# Turntable.net
KiCad netlist of a schematic drawn in EAGLE
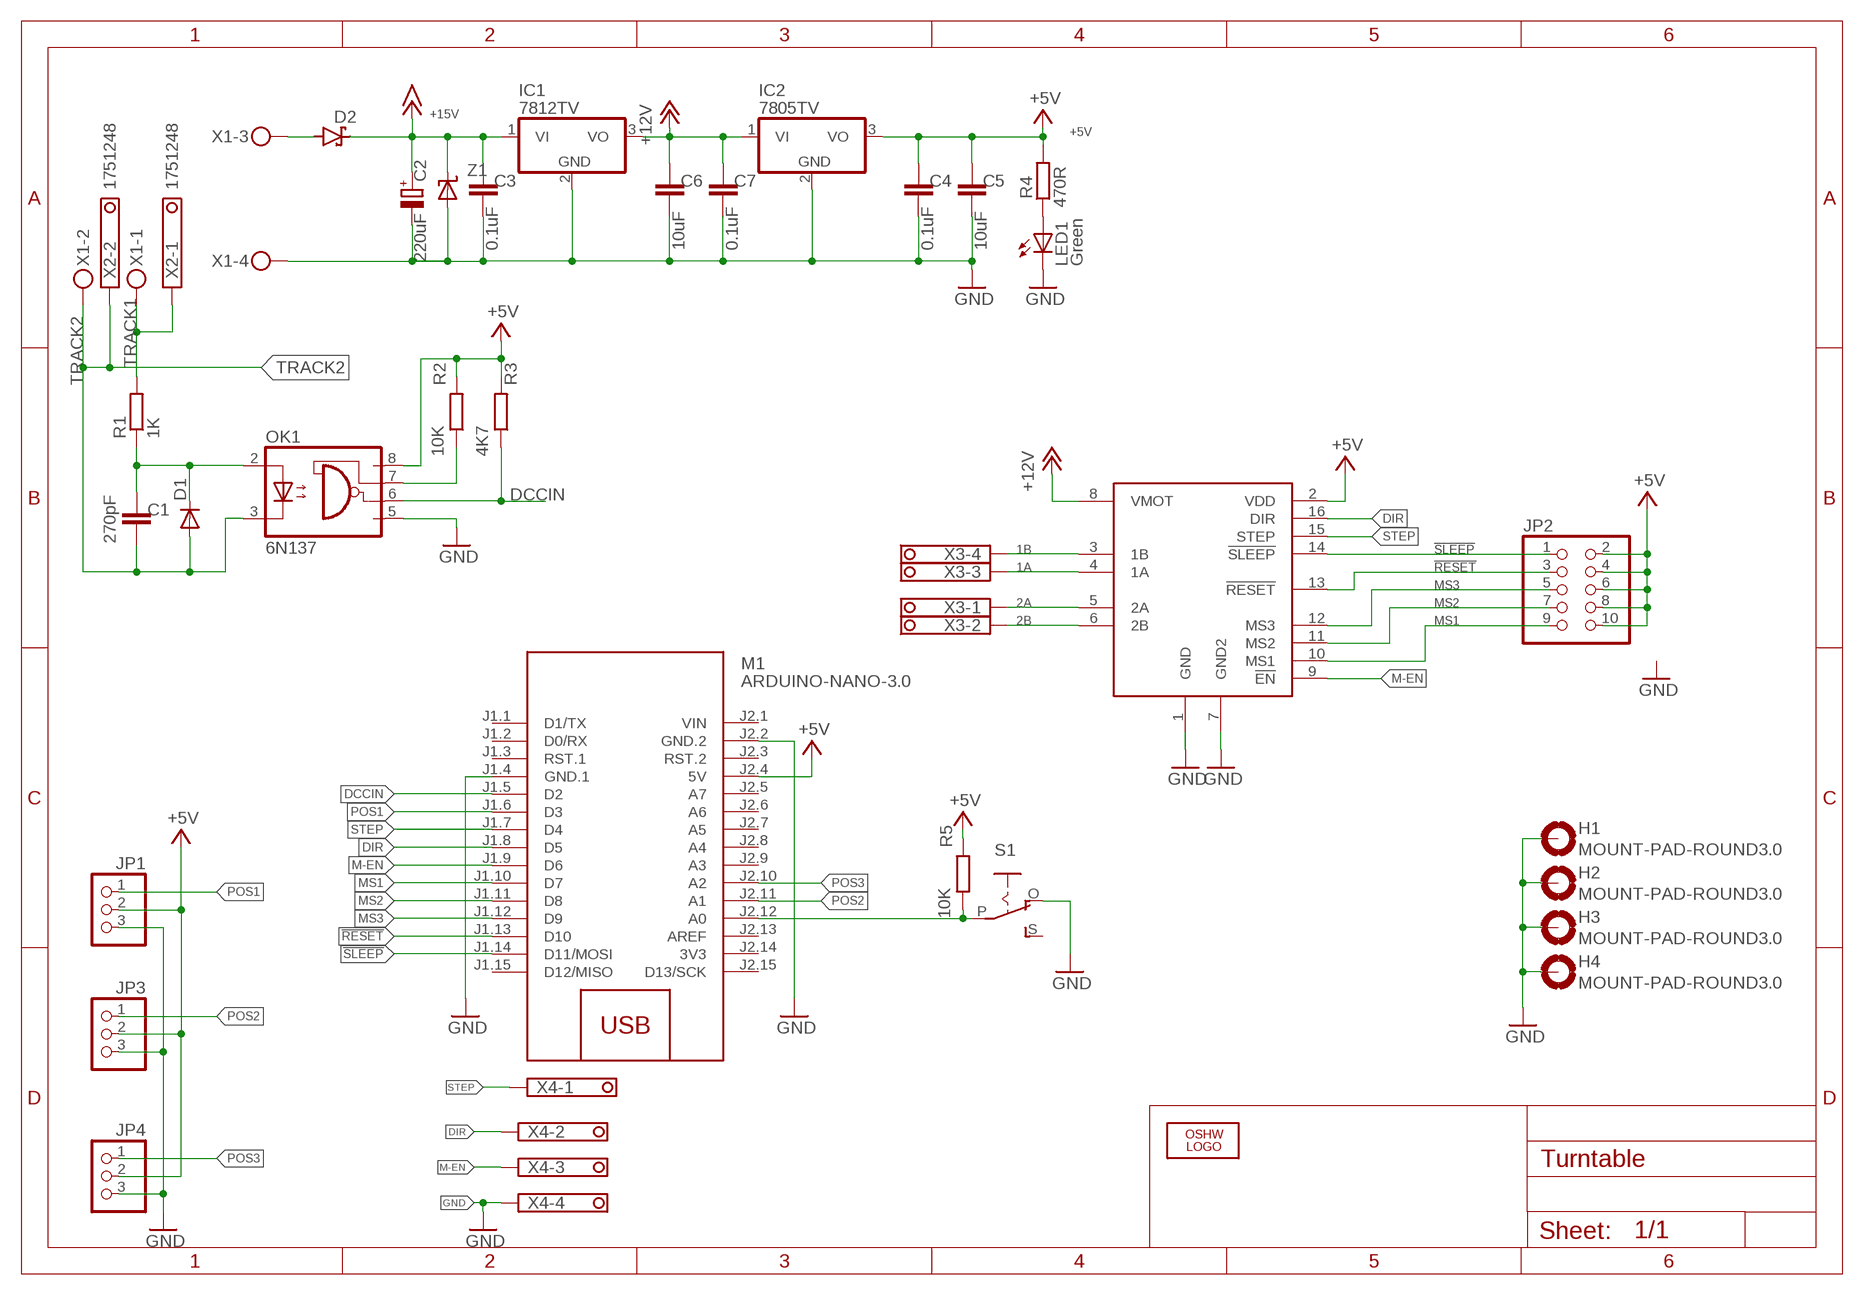
[diagram p0: schematic, sheet 1]

(export (version "E")
  (design (tool "Eeschema 10.0.6"))
  (components
    (comp (ref "C1")
      (value "270pF")
      (footprint "eagle-import:0805")
      (libsource (lib "eagle-import") (part "CAPACITOR-0805"))
    )
    (comp (ref "C2")
      (value "220uF")
      (footprint "eagle-import:E7,5-16")
      (libsource (lib "eagle-import") (part "CPOL-EUE7.5-16"))
    )
    (comp (ref "C3")
      (value "0.1uF")
      (footprint "eagle-import:0805")
      (libsource (lib "eagle-import") (part "CAPACITOR-0805"))
    )
    (comp (ref "C4")
      (value "0.1uF")
      (footprint "eagle-import:0805")
      (libsource (lib "eagle-import") (part "CAPACITOR-0805"))
    )
    (comp (ref "C5")
      (value "10uF")
      (footprint "eagle-import:0805")
      (libsource (lib "eagle-import") (part "CAPACITOR-0805"))
    )
    (comp (ref "C6")
      (value "10uF")
      (footprint "eagle-import:0805")
      (libsource (lib "eagle-import") (part "CAPACITOR-0805"))
    )
    (comp (ref "C7")
      (value "0.1uF")
      (footprint "eagle-import:0805")
      (libsource (lib "eagle-import") (part "CAPACITOR-0805"))
    )
    (comp (ref "D1")
      (value "CGRM4002-G")
      (footprint "eagle-import:SOD-123_MINI-SMA")
      (libsource (lib "eagle-import") (part "CGRM400-G2"))
    )
    (comp (ref "D2")
      (value "SCHOTTKY-DIODESMD")
      (footprint "eagle-import:SMB")
      (libsource (lib "eagle-import") (part "SCHOTTKY-DIODESMD"))
    )
    (comp (ref "H1")
      (value "MOUNT-PAD-ROUND3.0")
      (footprint "eagle-import:3,0-PAD")
      (libsource (lib "eagle-import") (part "MOUNT-PAD-ROUND3.0"))
    )
    (comp (ref "H2")
      (value "MOUNT-PAD-ROUND3.0")
      (footprint "eagle-import:3,0-PAD")
      (libsource (lib "eagle-import") (part "MOUNT-PAD-ROUND3.0"))
    )
    (comp (ref "H3")
      (value "MOUNT-PAD-ROUND3.0")
      (footprint "eagle-import:3,0-PAD")
      (libsource (lib "eagle-import") (part "MOUNT-PAD-ROUND3.0"))
    )
    (comp (ref "H4")
      (value "MOUNT-PAD-ROUND3.0")
      (footprint "eagle-import:3,0-PAD")
      (libsource (lib "eagle-import") (part "MOUNT-PAD-ROUND3.0"))
    )
    (comp (ref "IC1")
      (value "7812TV")
      (footprint "eagle-import:TO220V")
      (libsource (lib "eagle-import") (part "78TV12"))
    )
    (comp (ref "IC2")
      (value "7805TV")
      (footprint "eagle-import:TO220V")
      (libsource (lib "eagle-import") (part "78TV05"))
    )
    (comp (ref "JP1")
      (value "PINHD-1X3")
      (footprint "eagle-import:1X03")
      (libsource (lib "eagle-import") (part "PINHD-1X3"))
    )
    (comp (ref "JP2")
      (value "PINHD-2X5")
      (footprint "eagle-import:2X05")
      (libsource (lib "eagle-import") (part "PINHD-2X5"))
    )
    (comp (ref "JP3")
      (value "PINHD-1X3")
      (footprint "eagle-import:1X03")
      (libsource (lib "eagle-import") (part "PINHD-1X3"))
    )
    (comp (ref "JP4")
      (value "PINHD-1X3")
      (footprint "eagle-import:1X03")
      (libsource (lib "eagle-import") (part "PINHD-1X3"))
    )
    (comp (ref "LED1")
      (value "Green")
      (footprint "eagle-import:LED3MM")
      (libsource (lib "eagle-import") (part "LED3MM"))
    )
    (comp (ref "LOGO1")
      (value "OSHW_LOGO_6MILX0200-NT")
      (footprint "eagle-import:OSHW_6X200_NOTEXT")
      (libsource (lib "eagle-import") (part "OSHW_LOGO_6MILX0200-NT"))
    )
    (comp (ref "M1")
      (value "ARDUINO-NANO-3.0")
      (footprint "eagle-import:ARDUINO-NANO-3.0")
      (libsource (lib "eagle-import") (part "ARDUINO-NANO-3.0"))
    )
    (comp (ref "OK1")
      (value "6N137")
      (footprint "eagle-import:DIL08")
      (libsource (lib "eagle-import") (part "6N137"))
    )
    (comp (ref "R1")
      (value "1K")
      (footprint "eagle-import:R0805")
      (libsource (lib "eagle-import") (part "R-EU_R0805"))
    )
    (comp (ref "R2")
      (value "10K")
      (footprint "eagle-import:R0805")
      (libsource (lib "eagle-import") (part "R-EU_R0805"))
    )
    (comp (ref "R3")
      (value "4K7")
      (footprint "eagle-import:R0805")
      (libsource (lib "eagle-import") (part "R-EU_R0805"))
    )
    (comp (ref "R4")
      (value "470R")
      (footprint "eagle-import:R0805")
      (libsource (lib "eagle-import") (part "R-EU_R0805"))
    )
    (comp (ref "R5")
      (value "10K")
      (footprint "eagle-import:R0805")
      (libsource (lib "eagle-import") (part "R-EU_R0805"))
    )
    (comp (ref "S1")
      (value "EG1218S")
      (footprint "eagle-import:EG1218")
      (libsource (lib "eagle-import") (part "EG1218S"))
    )
    (comp (ref "U2")
      (value "A4988")
      (footprint "eagle-import:POLOLUA4988")
      (libsource (lib "eagle-import") (part "A4988"))
    )
    (comp (ref "X1")
      (value "MKDSN1,5/4-5,08")
      (footprint "eagle-import:MKDSN1,5_4-5,08")
      (fields (field (name "MPN") "SMKDSN1,5/4-5,08"))
      (libsource (lib "eagle-import") (part "MKDSN1,5/4-5,08"))
    )
    (comp (ref "X2")
      (value "1751248")
      (footprint "eagle-import:1751248")
      (libsource (lib "eagle-import") (part "1751248"))
    )
    (comp (ref "X3")
      (value "1751264")
      (footprint "eagle-import:1751264")
      (libsource (lib "eagle-import") (part "1751264"))
    )
    (comp (ref "X4")
      (value "1751264")
      (footprint "eagle-import:1751264")
      (libsource (lib "eagle-import") (part "1751264"))
    )
    (comp (ref "Z1")
      (value "TRANSZORB")
      (footprint "eagle-import:SMB")
      (fields (field (name "VOLTAGE") "15V"))
      (libsource (lib "eagle-import") (part "TRANSZORB"))
    )
  )
  (nets
    (net (code "1") (name "+5V") (class "Default")
      (node (ref "C4") (pin "1") (pinfunction "1_1") (pintype "passive"))
      (node (ref "C5") (pin "1") (pinfunction "1_1") (pintype "passive"))
      (node (ref "IC2") (pin "3") (pinfunction "VO_3") (pintype "passive"))
      (node (ref "JP1") (pin "2") (pinfunction "2_2") (pintype "passive"))
      (node (ref "JP2") (pin "10") (pinfunction "10_10") (pintype "passive"))
      (node (ref "JP2") (pin "2") (pinfunction "2_2") (pintype "passive"))
      (node (ref "JP2") (pin "4") (pinfunction "4_4") (pintype "passive"))
      (node (ref "JP2") (pin "6") (pinfunction "6_6") (pintype "passive"))
      (node (ref "JP2") (pin "8") (pinfunction "8_8") (pintype "passive"))
      (node (ref "JP3") (pin "2") (pinfunction "2_2") (pintype "passive"))
      (node (ref "JP4") (pin "2") (pinfunction "2_2") (pintype "passive"))
      (node (ref "M1") (pin "J2.4") (pinfunction "5V_J2.4") (pintype "power_in"))
      (node (ref "OK1") (pin "8") (pinfunction "VCC_8") (pintype "passive"))
      (node (ref "R2") (pin "2") (pinfunction "2_2") (pintype "passive"))
      (node (ref "R3") (pin "2") (pinfunction "2_2") (pintype "passive"))
      (node (ref "R4") (pin "2") (pinfunction "2_2") (pintype "passive"))
      (node (ref "R5") (pin "2") (pinfunction "2_2") (pintype "passive"))
      (node (ref "U2") (pin "2") (pinfunction "VDD_2") (pintype "power_in"))
    )
    (net (code "2") (name "+12V") (class "Default")
      (node (ref "C6") (pin "1") (pinfunction "1_1") (pintype "passive"))
      (node (ref "C7") (pin "1") (pinfunction "1_1") (pintype "passive"))
      (node (ref "IC1") (pin "3") (pinfunction "VO_3") (pintype "passive"))
      (node (ref "IC2") (pin "1") (pinfunction "VI_1") (pintype "input"))
      (node (ref "U2") (pin "8") (pinfunction "VMOT_8") (pintype "bidirectional"))
    )
    (net (code "3") (name "+15V") (class "Default")
      (node (ref "C2") (pin "+") (pinfunction "+_+") (pintype "passive"))
      (node (ref "C3") (pin "1") (pinfunction "1_1") (pintype "passive"))
      (node (ref "D2") (pin "C") (pinfunction "C_C") (pintype "passive"))
      (node (ref "IC1") (pin "1") (pinfunction "VI_1") (pintype "input"))
      (node (ref "Z1") (pin "1") (pinfunction "C_1") (pintype "passive"))
    )
    (net (code "4") (name "/1A") (class "Default")
      (node (ref "U2") (pin "4") (pinfunction "1A_4") (pintype "open_collector"))
      (node (ref "X3") (pin "3") (pinfunction "K_3") (pintype "passive"))
    )
    (net (code "5") (name "/1B") (class "Default")
      (node (ref "U2") (pin "3") (pinfunction "1B_3") (pintype "open_collector"))
      (node (ref "X3") (pin "4") (pinfunction "K_4") (pintype "passive"))
    )
    (net (code "6") (name "/2A") (class "Default")
      (node (ref "U2") (pin "5") (pinfunction "2A_5") (pintype "open_collector"))
      (node (ref "X3") (pin "1") (pinfunction "K_1") (pintype "passive"))
    )
    (net (code "7") (name "/2B") (class "Default")
      (node (ref "U2") (pin "6") (pinfunction "2B_6") (pintype "open_collector"))
      (node (ref "X3") (pin "2") (pinfunction "K_2") (pintype "passive"))
    )
    (net (code "8") (name "/3V3") (class "Default")
      (node (ref "M1") (pin "J2.14") (pinfunction "3V3_J2.14") (pintype "power_in"))
    )
    (net (code "9") (name "/TRACK1") (class "Default")
      (node (ref "R1") (pin "2") (pinfunction "2_2") (pintype "passive"))
      (node (ref "X1") (pin "1") (pinfunction "KL_1") (pintype "passive"))
      (node (ref "X2") (pin "1") (pinfunction "K_1") (pintype "passive"))
    )
    (net (code "10") (name "/VIN") (class "Default")
      (node (ref "M1") (pin "J2.1") (pinfunction "VIN_J2.1") (pintype "power_in"))
    )
    (net (code "11") (name "/~{RESET}") (class "Default")
      (node (ref "JP2") (pin "3") (pinfunction "3_3") (pintype "passive"))
      (node (ref "M1") (pin "J1.13") (pinfunction "D10_J1.13") (pintype "bidirectional"))
      (node (ref "U2") (pin "13") (pinfunction "~{RESET}_13") (pintype "input"))
    )
    (net (code "12") (name "/~{SLEEP}") (class "Default")
      (node (ref "JP2") (pin "1") (pinfunction "1_1") (pintype "passive"))
      (node (ref "M1") (pin "J1.14") (pinfunction "D11/MOSI_J1.14") (pintype "bidirectional"))
      (node (ref "U2") (pin "14") (pinfunction "~{SLEEP}_14") (pintype "input"))
    )
    (net (code "13") (name "DCCIN") (class "Default")
      (node (ref "M1") (pin "J1.5") (pinfunction "D2_J1.5") (pintype "bidirectional"))
      (node (ref "OK1") (pin "6") (pinfunction "VO_6") (pintype "passive"))
      (node (ref "R3") (pin "1") (pinfunction "1_1") (pintype "passive"))
    )
    (net (code "14") (name "DIR") (class "Default")
      (node (ref "M1") (pin "J1.8") (pinfunction "D5_J1.8") (pintype "bidirectional"))
      (node (ref "U2") (pin "16") (pinfunction "DIR_16") (pintype "input"))
      (node (ref "X4") (pin "2") (pinfunction "K_2") (pintype "passive"))
    )
    (net (code "15") (name "GND") (class "Default")
      (node (ref "C2") (pin "-") (pinfunction "-_-") (pintype "passive"))
      (node (ref "C3") (pin "2") (pinfunction "2_2") (pintype "passive"))
      (node (ref "C4") (pin "2") (pinfunction "2_2") (pintype "passive"))
      (node (ref "C5") (pin "2") (pinfunction "2_2") (pintype "passive"))
      (node (ref "C6") (pin "2") (pinfunction "2_2") (pintype "passive"))
      (node (ref "C7") (pin "2") (pinfunction "2_2") (pintype "passive"))
      (node (ref "H1") (pin "B3,0") (pinfunction "MOUNT_B3,0") (pintype "passive"))
      (node (ref "H2") (pin "B3,0") (pinfunction "MOUNT_B3,0") (pintype "passive"))
      (node (ref "H3") (pin "B3,0") (pinfunction "MOUNT_B3,0") (pintype "passive"))
      (node (ref "H4") (pin "B3,0") (pinfunction "MOUNT_B3,0") (pintype "passive"))
      (node (ref "IC1") (pin "2") (pinfunction "GND_2") (pintype "passive"))
      (node (ref "IC2") (pin "2") (pinfunction "GND_2") (pintype "passive"))
      (node (ref "JP1") (pin "3") (pinfunction "3_3") (pintype "passive"))
      (node (ref "JP3") (pin "3") (pinfunction "3_3") (pintype "passive"))
      (node (ref "JP4") (pin "3") (pinfunction "3_3") (pintype "passive"))
      (node (ref "LED1") (pin "K") (pinfunction "C_K") (pintype "passive"))
      (node (ref "M1") (pin "J1.4") (pinfunction "GND.1_J1.4") (pintype "power_in"))
      (node (ref "M1") (pin "J2.2") (pinfunction "GND.2_J2.2") (pintype "power_in"))
      (node (ref "OK1") (pin "5") (pinfunction "GND_5") (pintype "passive"))
      (node (ref "S1") (pin "O") (pinfunction "O_O") (pintype "passive"))
      (node (ref "U2") (pin "1") (pinfunction "GND_1") (pintype "passive"))
      (node (ref "U2") (pin "7") (pinfunction "GND2_7") (pintype "bidirectional"))
      (node (ref "X1") (pin "4") (pinfunction "KL_4") (pintype "passive"))
      (node (ref "X4") (pin "4") (pinfunction "K_4") (pintype "passive"))
      (node (ref "Z1") (pin "2") (pinfunction "A_2") (pintype "passive"))
    )
    (net (code "16") (name "M-EN") (class "Default")
      (node (ref "M1") (pin "J1.9") (pinfunction "D6_J1.9") (pintype "bidirectional"))
      (node (ref "U2") (pin "9") (pinfunction "~{EN}_9") (pintype "input"))
      (node (ref "X4") (pin "3") (pinfunction "K_3") (pintype "passive"))
    )
    (net (code "17") (name "MS1") (class "Default")
      (node (ref "JP2") (pin "9") (pinfunction "9_9") (pintype "passive"))
      (node (ref "M1") (pin "J1.10") (pinfunction "D7_J1.10") (pintype "bidirectional"))
      (node (ref "U2") (pin "10") (pinfunction "MS1_10") (pintype "input"))
    )
    (net (code "18") (name "MS2") (class "Default")
      (node (ref "JP2") (pin "7") (pinfunction "7_7") (pintype "passive"))
      (node (ref "M1") (pin "J1.11") (pinfunction "D8_J1.11") (pintype "bidirectional"))
      (node (ref "U2") (pin "11") (pinfunction "MS2_11") (pintype "input"))
    )
    (net (code "19") (name "MS3") (class "Default")
      (node (ref "JP2") (pin "5") (pinfunction "5_5") (pintype "passive"))
      (node (ref "M1") (pin "J1.12") (pinfunction "D9_J1.12") (pintype "bidirectional"))
      (node (ref "U2") (pin "12") (pinfunction "MS3_12") (pintype "input"))
    )
    (net (code "20") (name "Net-(LED1-PadA)") (class "Default")
      (node (ref "LED1") (pin "A") (pinfunction "A_A") (pintype "passive"))
      (node (ref "R4") (pin "1") (pinfunction "1_1") (pintype "passive"))
    )
    (net (code "21") (name "Net-(M1-A0)") (class "Default")
      (node (ref "M1") (pin "J2.12") (pinfunction "A0_J2.12") (pintype "bidirectional"))
      (node (ref "R5") (pin "1") (pinfunction "1_1") (pintype "passive"))
      (node (ref "S1") (pin "P") (pinfunction "P_P") (pintype "passive"))
    )
    (net (code "22") (name "Net-(OK1-A)") (class "Default")
      (node (ref "C1") (pin "1") (pinfunction "1_1") (pintype "passive"))
      (node (ref "D1") (pin "C") (pinfunction "C_C") (pintype "passive"))
      (node (ref "OK1") (pin "2") (pinfunction "A_2") (pintype "passive"))
      (node (ref "R1") (pin "1") (pinfunction "1_1") (pintype "passive"))
    )
    (net (code "23") (name "Net-(OK1-VE)") (class "Default")
      (node (ref "OK1") (pin "7") (pinfunction "VE_7") (pintype "passive"))
      (node (ref "R2") (pin "1") (pinfunction "1_1") (pintype "passive"))
    )
    (net (code "24") (name "Net-(X1C-KL)") (class "Default")
      (node (ref "D2") (pin "A") (pinfunction "A_A") (pintype "passive"))
      (node (ref "X1") (pin "3") (pinfunction "KL_3") (pintype "passive"))
    )
    (net (code "25") (name "POS1") (class "Default")
      (node (ref "JP1") (pin "1") (pinfunction "1_1") (pintype "passive"))
      (node (ref "M1") (pin "J1.6") (pinfunction "D3_J1.6") (pintype "bidirectional"))
    )
    (net (code "26") (name "POS2") (class "Default")
      (node (ref "JP3") (pin "1") (pinfunction "1_1") (pintype "passive"))
      (node (ref "M1") (pin "J2.11") (pinfunction "A1_J2.11") (pintype "bidirectional"))
    )
    (net (code "27") (name "POS3") (class "Default")
      (node (ref "JP4") (pin "1") (pinfunction "1_1") (pintype "passive"))
      (node (ref "M1") (pin "J2.10") (pinfunction "A2_J2.10") (pintype "bidirectional"))
    )
    (net (code "28") (name "STEP") (class "Default")
      (node (ref "M1") (pin "J1.7") (pinfunction "D4_J1.7") (pintype "bidirectional"))
      (node (ref "U2") (pin "15") (pinfunction "STEP_15") (pintype "input"))
      (node (ref "X4") (pin "1") (pinfunction "K_1") (pintype "passive"))
    )
    (net (code "29") (name "TRACK2") (class "Default")
      (node (ref "C1") (pin "2") (pinfunction "2_2") (pintype "passive"))
      (node (ref "D1") (pin "A") (pinfunction "A_A") (pintype "passive"))
      (node (ref "OK1") (pin "3") (pinfunction "C_3") (pintype "passive"))
      (node (ref "X1") (pin "2") (pinfunction "KL_2") (pintype "passive"))
      (node (ref "X2") (pin "2") (pinfunction "K_2") (pintype "passive"))
    )
    (net (code "30") (name "unconnected-(M1-A3-PadJ2.9)") (class "Default")
      (node (ref "M1") (pin "J2.9") (pinfunction "A3_J2.9") (pintype "bidirectional"))
    )
    (net (code "31") (name "unconnected-(M1-A4-PadJ2.8)") (class "Default")
      (node (ref "M1") (pin "J2.8") (pinfunction "A4_J2.8") (pintype "bidirectional"))
    )
    (net (code "32") (name "unconnected-(M1-A5-PadJ2.7)") (class "Default")
      (node (ref "M1") (pin "J2.7") (pinfunction "A5_J2.7") (pintype "bidirectional"))
    )
    (net (code "33") (name "unconnected-(M1-A6-PadJ2.6)") (class "Default")
      (node (ref "M1") (pin "J2.6") (pinfunction "A6_J2.6") (pintype "bidirectional"))
    )
    (net (code "34") (name "unconnected-(M1-A7-PadJ2.5)") (class "Default")
      (node (ref "M1") (pin "J2.5") (pinfunction "A7_J2.5") (pintype "bidirectional"))
    )
    (net (code "35") (name "unconnected-(M1-AREF-PadJ2.13)") (class "Default")
      (node (ref "M1") (pin "J2.13") (pinfunction "AREF_J2.13") (pintype "bidirectional"))
    )
    (net (code "36") (name "unconnected-(M1-D0{slash}RX-PadJ1.2)") (class "Default")
      (node (ref "M1") (pin "J1.2") (pinfunction "D0/RX_J1.2") (pintype "bidirectional"))
    )
    (net (code "37") (name "unconnected-(M1-D1{slash}TX-PadJ1.1)") (class "Default")
      (node (ref "M1") (pin "J1.1") (pinfunction "D1/TX_J1.1") (pintype "bidirectional"))
    )
    (net (code "38") (name "unconnected-(M1-D12{slash}MISO-PadJ1.15)") (class "Default")
      (node (ref "M1") (pin "J1.15") (pinfunction "D12/MISO_J1.15") (pintype "bidirectional"))
    )
    (net (code "39") (name "unconnected-(M1-D13{slash}SCK-PadJ2.15)") (class "Default")
      (node (ref "M1") (pin "J2.15") (pinfunction "D13/SCK_J2.15") (pintype "bidirectional"))
    )
    (net (code "40") (name "unconnected-(M1-RST.1-PadJ1.3)") (class "Default")
      (node (ref "M1") (pin "J1.3") (pinfunction "RST.1_J1.3") (pintype "bidirectional"))
    )
    (net (code "41") (name "unconnected-(M1-RST.2-PadJ2.3)") (class "Default")
      (node (ref "M1") (pin "J2.3") (pinfunction "RST.2_J2.3") (pintype "bidirectional"))
    )
    (net (code "42") (name "unconnected-(S1-PadS)") (class "Default")
      (node (ref "S1") (pin "S") (pinfunction "S_S") (pintype "passive"))
    )
  )
)
